# Sheet_1_2022-02-26.net
KiCad netlist of a schematic drawn in Altium Designer
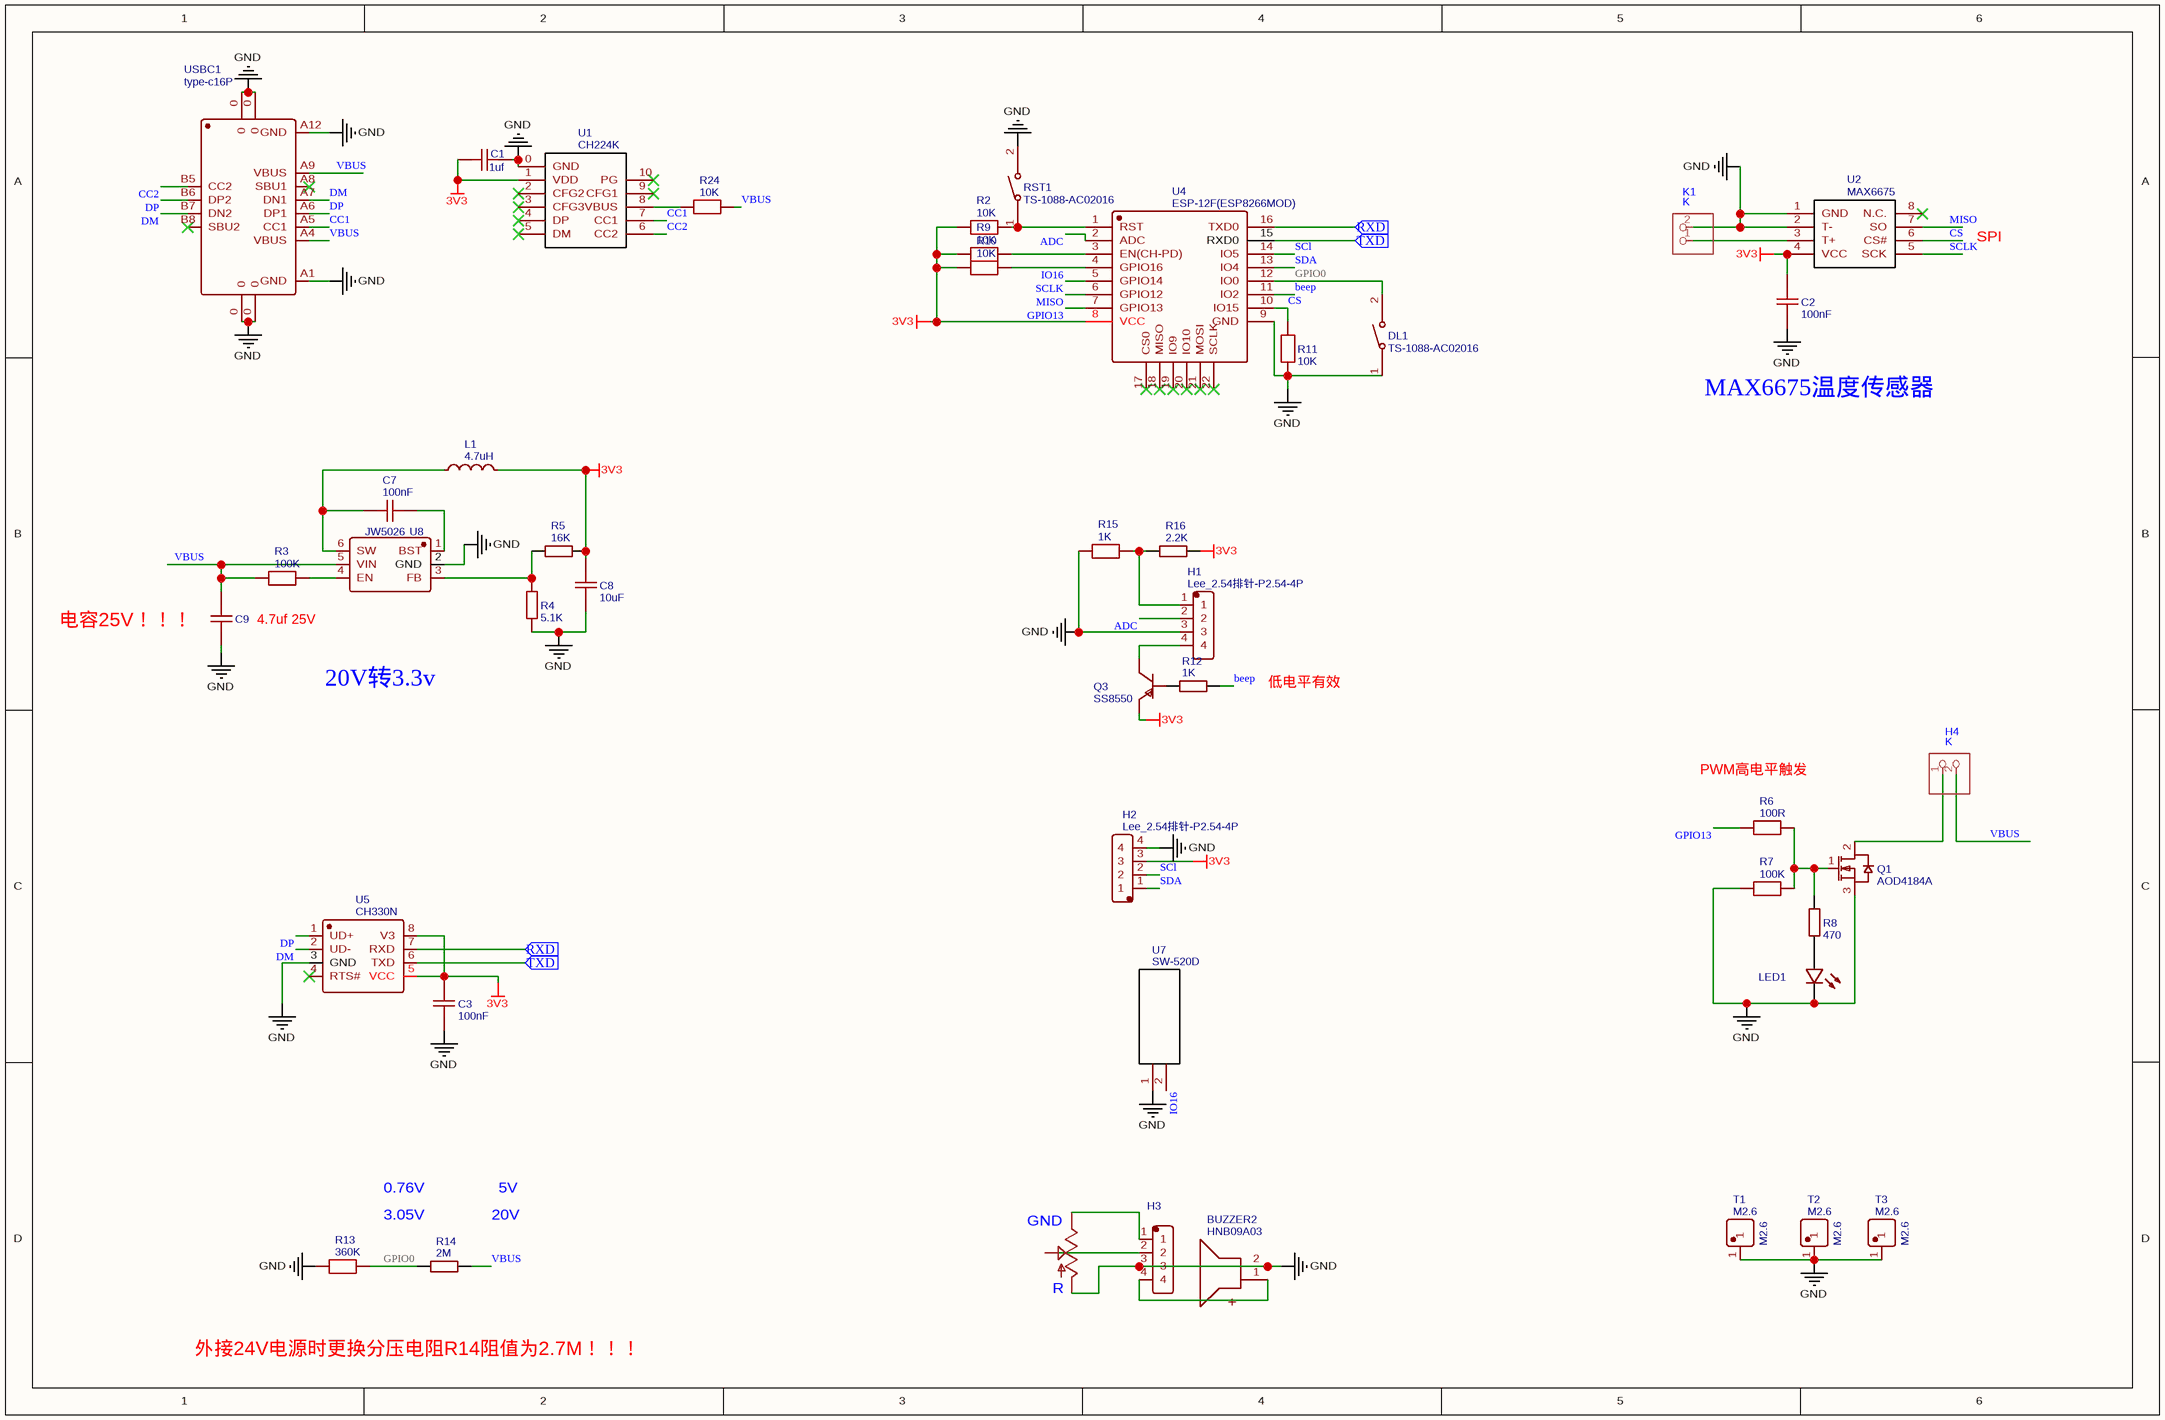
[diagram p0: Sheet_1_2022-02-26.schdoc]

(export (version "E")
  (design (tool "Eeschema 10.0.6"))
  (components
    (comp (ref "BUZZER2")
      (value "HNB09A03")
      (fields (field (name "BOM_SUPPLIER PART") "C96102") (field (name "CONTRIBUTOR") "LCSC"))
      (libsource (lib "altium-import") (part "root_0_HNB09A03_"))
    )
    (comp (ref "C1")
      (value "1uf")
      (fields (field (name "BOM_SUPPLIER PART") "C2887020") (field (name "CONTRIBUTOR") "LCEDA_Lib"))
      (libsource (lib "altium-import") (part "root_2_1uf_"))
    )
    (comp (ref "C2")
      (value "100nF")
      (fields
        (field (name "BOM_SUPPLIER PART") "C387959")
        (field (name "BOM_MANUFACTURER PART") "0402X104K500CT")
        (field (name "CONTRIBUTOR") "LCSC")
      )
      (libsource (lib "altium-import") (part "root_2_100nF_"))
    )
    (comp (ref "C3")
      (value "100nF")
      (fields
        (field (name "BOM_SUPPLIER PART") "C387959")
        (field (name "BOM_MANUFACTURER PART") "0402X104K500CT")
        (field (name "CONTRIBUTOR") "LCSC")
      )
      (libsource (lib "altium-import") (part "root_2_100nF_"))
    )
    (comp (ref "C7")
      (value "100nF")
      (fields
        (field (name "BOM_SUPPLIER PART") "C387959")
        (field (name "BOM_MANUFACTURER PART") "0402X104K500CT")
        (field (name "CONTRIBUTOR") "LCSC")
      )
      (libsource (lib "altium-import") (part "root_1_100nF_"))
    )
    (comp (ref "C8")
      (value "10uF")
      (fields
        (field (name "BOM_SUPPLIER PART") "C315248")
        (field (name "BOM_MANUFACTURER PART") "CL05A106MP5NUNC")
        (field (name "CONTRIBUTOR") "LCSC")
      )
      (libsource (lib "altium-import") (part "root_1_10uF_"))
    )
    (comp (ref "C9")
      (value "4.7uf 25V")
      (fields (field (name "BOM_SUPPLIER PART") "C2858031") (field (name "CONTRIBUTOR") "LCEDA_Lib"))
      (libsource (lib "altium-import") (part "root_1_4.7uf 25V_"))
    )
    (comp (ref "DL1")
      (value "TS-1088-AC02016")
      (fields (field (name "BOM_SUPPLIER PART") "C720475") (field (name "CONTRIBUTOR") "LCSC"))
      (libsource (lib "altium-import") (part "root_1_TS-1088-AC02016_"))
    )
    (comp (ref "H1")
      (value "Lee_2.54排针-P2.54-4P")
      (fields
        (field (name "BOM_MANUFACTURER PART") "210S-1*4P L=11.6MMGold-plated black")
        (field (name "BOM_SUPPLIER PART") "C124378")
        (field (name "CONTRIBUTOR") "EdwardLee2020")
      )
      (libsource (lib "altium-import") (part "root_0_Lee_2.54排针-P2.54-4P_"))
    )
    (comp (ref "H2")
      (value "Lee_2.54排针-P2.54-4P")
      (fields
        (field (name "BOM_MANUFACTURER PART") "210S-1*4P L=11.6MMGold-plated black")
        (field (name "BOM_SUPPLIER PART") "C124378")
        (field (name "CONTRIBUTOR") "EdwardLee2020")
      )
      (libsource (lib "altium-import") (part "root_2_Lee_2.54排针-P2.54-4P_"))
    )
    (comp (ref "H3")
      (value "Lee_2.54排针-P2.54-4P")
      (fields
        (field (name "BOM_MANUFACTURER PART") "210S-1*4P L=11.6MMGold-plated black")
        (field (name "BOM_SUPPLIER PART") "C124378")
        (field (name "CONTRIBUTOR") "EdwardLee2020")
      )
      (libsource (lib "altium-import") (part "root_0_Lee_2.54排针-P2.54-4P_"))
    )
    (comp (ref "H4")
      (value "K")
      (fields (field (name "BOM_MANUFACTURER PART") "826629-2") (field (name "BOM_SUPPLIER PART") "C86471"))
      (libsource (lib "altium-import") (part "root_1_K_"))
    )
    (comp (ref "K1")
      (value "K")
      (fields (field (name "BOM_MANUFACTURER PART") "826629-2") (field (name "BOM_SUPPLIER PART") "C86471"))
      (libsource (lib "altium-import") (part "root_2_K_"))
    )
    (comp (ref "L1")
      (value "4.7uH")
      (fields
        (field (name "BOM_MANUFACTURER PART") "SWPA252012S4R7MT")
        (field (name "BOM_SUPPLIER PART") "C87640")
      )
      (libsource (lib "altium-import") (part "root_0_4.7uH_"))
    )
    (comp (ref "LED1")
      (value "19-217/GHC-YR1S2/3T")
      (fields (field (name "BOM_SUPPLIER PART") "C181863"))
      (libsource (lib "altium-import") (part "root_3_19-217/GHC-YR1S2/3T_"))
    )
    (comp (ref "Q1")
      (value "AOD4184A")
      (fields (field (name "BOM_SUPPLIER PART") "C99124") (field (name "CONTRIBUTOR") "LCSC"))
      (libsource (lib "altium-import") (part "root_0_AOD4184A_"))
    )
    (comp (ref "Q3")
      (value "SS8550")
      (fields (field (name "BOM_SUPPLIER PART") "C266595") (field (name "CONTRIBUTOR") "SmileWJ"))
      (libsource (lib "altium-import") (part "root_2_SS8550_"))
    )
    (comp (ref "R2")
      (value "10K")
      (fields
        (field (name "BOM_SUPPLIER PART") "C830216")
        (field (name "BOM_MANUFACTURER PART") "RK73G1ETTP1002F")
        (field (name "CONTRIBUTOR") "LCSC")
      )
      (libsource (lib "altium-import") (part "root_0_10K_"))
    )
    (comp (ref "R3")
      (value "100K")
      (fields
        (field (name "BOM_SUPPLIER PART") "C606167")
        (field (name "BOM_MANUFACTURER PART") "RC0402FR-7W100KL")
        (field (name "CONTRIBUTOR") "LCSC")
      )
      (libsource (lib "altium-import") (part "root_0_100K_"))
    )
    (comp (ref "R4")
      (value "5.1K")
      (fields (field (name "BOM_SUPPLIER PART") "C25905") (field (name "CONTRIBUTOR") "LCSC"))
      (libsource (lib "altium-import") (part "root_1_5.1K_"))
    )
    (comp (ref "R5")
      (value "16K")
      (fields
        (field (name "BOM_MANUFACTURER PART") "0402WGF7501TCE")
        (field (name "BOM_SUPPLIER PART") "C226690")
      )
      (libsource (lib "altium-import") (part "root_0_16K_"))
    )
    (comp (ref "R6")
      (value "100R")
      (fields
        (field (name "BOM_SUPPLIER PART") "C705641")
        (field (name "BOM_MANUFACTURER PART") "RT0402BRE07100RL")
        (field (name "CONTRIBUTOR") "LCSC")
      )
      (libsource (lib "altium-import") (part "root_0_100R_"))
    )
    (comp (ref "R7")
      (value "100K")
      (fields
        (field (name "BOM_SUPPLIER PART") "C606167")
        (field (name "BOM_MANUFACTURER PART") "RC0402FR-7W100KL")
        (field (name "CONTRIBUTOR") "LCSC")
      )
      (libsource (lib "altium-import") (part "root_0_100K_"))
    )
    (comp (ref "R8")
      (value "470")
      (fields
        (field (name "BOM_MANUFACTURER PART") "0805W8F1002T5E")
        (field (name "BOM_SUPPLIER PART") "C17414")
      )
      (libsource (lib "altium-import") (part "root_3_470_"))
    )
    (comp (ref "R9")
      (value "10K")
      (fields
        (field (name "BOM_SUPPLIER PART") "C830216")
        (field (name "BOM_MANUFACTURER PART") "RK73G1ETTP1002F")
        (field (name "CONTRIBUTOR") "LCSC")
      )
      (libsource (lib "altium-import") (part "root_0_10K_"))
    )
    (comp (ref "R10")
      (value "10K")
      (fields
        (field (name "BOM_SUPPLIER PART") "C830216")
        (field (name "BOM_MANUFACTURER PART") "RK73G1ETTP1002F")
        (field (name "CONTRIBUTOR") "LCSC")
      )
      (libsource (lib "altium-import") (part "root_0_10K_"))
    )
    (comp (ref "R11")
      (value "10K")
      (fields
        (field (name "BOM_SUPPLIER PART") "C830216")
        (field (name "BOM_MANUFACTURER PART") "RK73G1ETTP1002F")
        (field (name "CONTRIBUTOR") "LCSC")
      )
      (libsource (lib "altium-import") (part "root_1_10K_"))
    )
    (comp (ref "R12")
      (value "1K")
      (fields
        (field (name "BOM_MANUFACTURER PART") "0805W8F1002T5E")
        (field (name "BOM_SUPPLIER PART") "C17414")
      )
      (libsource (lib "altium-import") (part "root_2_1K_"))
    )
    (comp (ref "R13")
      (value "360K")
      (fields
        (field (name "BOM_SUPPLIER PART") "C482154")
        (field (name "BOM_MANUFACTURER PART") "CRCW0402360KFKED")
        (field (name "CONTRIBUTOR") "LCSC")
      )
      (libsource (lib "altium-import") (part "root_0_360K_"))
    )
    (comp (ref "R14")
      (value "2M")
      (fields
        (field (name "BOM_MANUFACTURER PART") "0402WGF2004TCE")
        (field (name "BOM_SUPPLIER PART") "C11512")
      )
      (libsource (lib "altium-import") (part "root_0_2M_"))
    )
    (comp (ref "R15")
      (value "1K")
      (fields
        (field (name "BOM_SUPPLIER PART") "C226698")
        (field (name "BOM_MANUFACTURER PART") "AC0402DR-071KL")
        (field (name "CONTRIBUTOR") "LCSC")
      )
      (libsource (lib "altium-import") (part "root_0_1K_"))
    )
    (comp (ref "R16")
      (value "2.2K")
      (fields
        (field (name "BOM_MANUFACTURER PART") "0402WGF2201TCE")
        (field (name "BOM_SUPPLIER PART") "C25879")
      )
      (libsource (lib "altium-import") (part "root_0_2.2K_"))
    )
    (comp (ref "R24")
      (value "10K")
      (fields
        (field (name "BOM_SUPPLIER PART") "C830216")
        (field (name "BOM_MANUFACTURER PART") "RK73G1ETTP1002F")
        (field (name "CONTRIBUTOR") "LCSC")
      )
      (libsource (lib "altium-import") (part "root_0_10K_"))
    )
    (comp (ref "RST1")
      (value "TS-1088-AC02016")
      (fields (field (name "BOM_SUPPLIER PART") "C720475") (field (name "CONTRIBUTOR") "LCSC"))
      (libsource (lib "altium-import") (part "root_1_TS-1088-AC02016_"))
    )
    (comp (ref "T1")
      (value "M2.6")
      (fields (field (name "CONTRIBUTOR") "wowlkh"))
      (libsource (lib "altium-import") (part "root_1_M2.6_"))
    )
    (comp (ref "T2")
      (value "M2.6")
      (fields (field (name "CONTRIBUTOR") "wowlkh"))
      (libsource (lib "altium-import") (part "root_1_M2.6_"))
    )
    (comp (ref "T3")
      (value "M2.6")
      (fields (field (name "CONTRIBUTOR") "wowlkh"))
      (libsource (lib "altium-import") (part "root_1_M2.6_"))
    )
    (comp (ref "U1")
      (value "CH224K")
      (fields (field (name "CONTRIBUTOR") "hans_1024"))
      (libsource (lib "altium-import") (part "root_0_CH224K_"))
    )
    (comp (ref "U2")
      (value "MAX6675")
      (fields
        (field (name "BOM_MANUFACTURER PART") "MAX6675ISA+T")
        (field (name "BOM_SUPPLIER PART") "C16030")
      )
      (libsource (lib "altium-import") (part "root_0_MAX6675_"))
    )
    (comp (ref "U4")
      (value "ESP-12F(ESP8266MOD)")
      (fields (field (name "BOM_SUPPLIER PART") "C82891"))
      (libsource (lib "altium-import") (part "root_0_ESP-12F(ESP8266MOD)_"))
    )
    (comp (ref "U5")
      (value "CH330N")
      (fields (field (name "BOM_SUPPLIER PART") "C108996"))
      (libsource (lib "altium-import") (part "root_0_CH330N_"))
    )
    (comp (ref "U7")
      (value "SW-520D")
      (fields (field (name "CONTRIBUTOR") "jimson.hu"))
      (libsource (lib "altium-import") (part "root_0_SW-520D_"))
    )
    (comp (ref "U8")
      (value "JW5026")
      (fields (field (name "BOM_SUPPLIER PART") "C185109") (field (name "CONTRIBUTOR") "LCSC"))
      (libsource (lib "altium-import") (part "root_0_JW5026_"))
    )
    (comp (ref "U10")
      (value "B103单联")
      (fields (field (name "CONTRIBUTOR") "lualiliu"))
      (libsource (lib "altium-import") (part "root_2_B103单联_"))
    )
    (comp (ref "USBC1")
      (value "type-c16P")
      (fields (field (name "BOM_SUPPLIER PART") "C167321") (field (name "CONTRIBUTOR") "LCSC"))
      (libsource (lib "altium-import") (part "root_0_type-c16P_"))
    )
  )
  (nets
    (net (code "1") (name "/ADC") (class "Default")
      (node (ref "H1") (pin "2") (pinfunction "2_2") (pintype "passive"))
      (node (ref "U4") (pin "2") (pinfunction "ADC_2") (pintype "passive"))
    )
    (net (code "2") (name "/CC1") (class "Default")
      (node (ref "U1") (pin "7") (pinfunction "CC1_7") (pintype "passive"))
      (node (ref "USBC1") (pin "A5") (pinfunction "CC1_A5") (pintype "passive"))
    )
    (net (code "3") (name "/CC2") (class "Default")
      (node (ref "U1") (pin "6") (pinfunction "CC2_6") (pintype "passive"))
      (node (ref "USBC1") (pin "B5") (pinfunction "CC2_B5") (pintype "passive"))
    )
    (net (code "4") (name "/CS") (class "Default")
      (node (ref "R11") (pin "2") (pinfunction "2_2") (pintype "passive"))
      (node (ref "U2") (pin "6") (pinfunction "CS#_6") (pintype "passive"))
      (node (ref "U4") (pin "10") (pinfunction "IO15_10") (pintype "passive"))
    )
    (net (code "5") (name "/DM") (class "Default")
      (node (ref "U5") (pin "2") (pinfunction "UD-_2") (pintype "passive"))
      (node (ref "USBC1") (pin "A7") (pinfunction "DN1_A7") (pintype "passive"))
      (node (ref "USBC1") (pin "B7") (pinfunction "DN2_B7") (pintype "passive"))
    )
    (net (code "6") (name "/DP") (class "Default")
      (node (ref "U5") (pin "1") (pinfunction "UD+_1") (pintype "passive"))
      (node (ref "USBC1") (pin "A6") (pinfunction "DP1_A6") (pintype "passive"))
      (node (ref "USBC1") (pin "B6") (pinfunction "DP2_B6") (pintype "passive"))
    )
    (net (code "7") (name "/GPIO0") (class "Default")
      (node (ref "DL1") (pin "2") (pinfunction "2_2") (pintype "passive"))
      (node (ref "R13") (pin "2") (pinfunction "2_2") (pintype "passive"))
      (node (ref "R14") (pin "1") (pinfunction "1_1") (pintype "passive"))
      (node (ref "U4") (pin "12") (pinfunction "IO0_12") (pintype "passive"))
    )
    (net (code "8") (name "/GPIO13") (class "Default")
      (node (ref "R6") (pin "1") (pinfunction "1_1") (pintype "passive"))
      (node (ref "U4") (pin "7") (pinfunction "GPIO13_7") (pintype "passive"))
    )
    (net (code "9") (name "/IO16") (class "Default")
      (node (ref "R10") (pin "2") (pinfunction "2_2") (pintype "passive"))
      (node (ref "U4") (pin "4") (pinfunction "GPIO16_4") (pintype "passive"))
      (node (ref "U7") (pin "2") (pinfunction "2_2") (pintype "passive"))
    )
    (net (code "10") (name "/MISO") (class "Default")
      (node (ref "U2") (pin "7") (pinfunction "SO_7") (pintype "passive"))
      (node (ref "U4") (pin "6") (pinfunction "GPIO12_6") (pintype "passive"))
    )
    (net (code "11") (name "/RXD") (class "Default")
      (node (ref "U4") (pin "16") (pinfunction "TXD0_16") (pintype "passive"))
      (node (ref "U5") (pin "7") (pinfunction "RXD_7") (pintype "passive"))
    )
    (net (code "12") (name "/SCLK") (class "Default")
      (node (ref "U2") (pin "5") (pinfunction "SCK_5") (pintype "passive"))
      (node (ref "U4") (pin "5") (pinfunction "GPIO14_5") (pintype "passive"))
    )
    (net (code "13") (name "/SCl") (class "Default")
      (node (ref "H2") (pin "2") (pinfunction "2_2") (pintype "passive"))
      (node (ref "U4") (pin "14") (pinfunction "IO5_14") (pintype "passive"))
    )
    (net (code "14") (name "/SDA") (class "Default")
      (node (ref "H2") (pin "1") (pinfunction "1_1") (pintype "passive"))
      (node (ref "U4") (pin "13") (pinfunction "IO4_13") (pintype "passive"))
    )
    (net (code "15") (name "/TXD") (class "Default")
      (node (ref "U4") (pin "15") (pinfunction "RXD0_15") (pintype "passive"))
      (node (ref "U5") (pin "6") (pinfunction "TXD_6") (pintype "passive"))
    )
    (net (code "16") (name "/VBUS") (class "Default")
      (node (ref "C9") (pin "2") (pinfunction "2_2") (pintype "passive"))
      (node (ref "H4") (pin "2") (pinfunction "2_2") (pintype "passive"))
      (node (ref "R14") (pin "2") (pinfunction "2_2") (pintype "passive"))
      (node (ref "R24") (pin "2") (pinfunction "2_2") (pintype "passive"))
      (node (ref "R3") (pin "1") (pinfunction "1_1") (pintype "passive"))
      (node (ref "U8") (pin "5") (pinfunction "VIN_5") (pintype "passive"))
      (node (ref "USBC1") (pin "A4") (pinfunction "VBUS_A4") (pintype "passive"))
      (node (ref "USBC1") (pin "A9") (pinfunction "VBUS_A9") (pintype "passive"))
    )
    (net (code "17") (name "/beep") (class "Default")
      (node (ref "R12") (pin "1") (pinfunction "1_1") (pintype "passive"))
      (node (ref "U4") (pin "11") (pinfunction "IO2_11") (pintype "passive"))
    )
    (net (code "18") (name "3V3") (class "Default")
      (node (ref "C1") (pin "2") (pinfunction "2_2") (pintype "passive"))
      (node (ref "C2") (pin "1") (pinfunction "1_1") (pintype "passive"))
      (node (ref "C3") (pin "1") (pinfunction "1_1") (pintype "passive"))
      (node (ref "C8") (pin "2") (pinfunction "2_2") (pintype "passive"))
      (node (ref "H2") (pin "3") (pinfunction "3_3") (pintype "passive"))
      (node (ref "L1") (pin "2") (pinfunction "2_2") (pintype "passive"))
      (node (ref "Q3") (pin "3") (pinfunction "C_3") (pintype "passive"))
      (node (ref "R10") (pin "1") (pinfunction "1_1") (pintype "passive"))
      (node (ref "R16") (pin "2") (pinfunction "2_2") (pintype "passive"))
      (node (ref "R2") (pin "1") (pinfunction "1_1") (pintype "passive"))
      (node (ref "R5") (pin "2") (pinfunction "2_2") (pintype "passive"))
      (node (ref "R9") (pin "1") (pinfunction "1_1") (pintype "passive"))
      (node (ref "U1") (pin "1") (pinfunction "VDD_1") (pintype "passive"))
      (node (ref "U2") (pin "4") (pinfunction "VCC_4") (pintype "passive"))
      (node (ref "U4") (pin "8") (pinfunction "VCC_8") (pintype "passive"))
      (node (ref "U5") (pin "5") (pinfunction "VCC_5") (pintype "passive"))
      (node (ref "U5") (pin "8") (pinfunction "V3_8") (pintype "passive"))
    )
    (net (code "19") (name "GND") (class "Default")
      (node (ref "BUZZER2") (pin "2") (pinfunction "-_2") (pintype "passive"))
      (node (ref "C1") (pin "1") (pinfunction "1_1") (pintype "passive"))
      (node (ref "C2") (pin "2") (pinfunction "2_2") (pintype "passive"))
      (node (ref "C3") (pin "2") (pinfunction "2_2") (pintype "passive"))
      (node (ref "C8") (pin "1") (pinfunction "1_1") (pintype "passive"))
      (node (ref "C9") (pin "1") (pinfunction "1_1") (pintype "passive"))
      (node (ref "DL1") (pin "1") (pinfunction "1_1") (pintype "passive"))
      (node (ref "H1") (pin "3") (pinfunction "3_3") (pintype "passive"))
      (node (ref "H2") (pin "4") (pinfunction "4_4") (pintype "passive"))
      (node (ref "H3") (pin "3") (pinfunction "3_3") (pintype "passive"))
      (node (ref "K1") (pin "2") (pinfunction "2_2") (pintype "passive"))
      (node (ref "LED1") (pin "2") (pinfunction "C_2") (pintype "passive"))
      (node (ref "Q1") (pin "3") (pinfunction "S_3") (pintype "passive"))
      (node (ref "R11") (pin "1") (pinfunction "1_1") (pintype "passive"))
      (node (ref "R13") (pin "1") (pinfunction "1_1") (pintype "passive"))
      (node (ref "R15") (pin "1") (pinfunction "1_1") (pintype "passive"))
      (node (ref "R4") (pin "1") (pinfunction "1_1") (pintype "passive"))
      (node (ref "R7") (pin "1") (pinfunction "1_1") (pintype "passive"))
      (node (ref "RST1") (pin "2") (pinfunction "2_2") (pintype "passive"))
      (node (ref "T1") (pin "1") (pinfunction "1_1") (pintype "passive"))
      (node (ref "T2") (pin "1") (pinfunction "1_1") (pintype "passive"))
      (node (ref "T3") (pin "1") (pinfunction "1_1") (pintype "passive"))
      (node (ref "U1") (pin "0") (pinfunction "GND_0") (pintype "passive"))
      (node (ref "U10") (pin "3") (pinfunction "A_3") (pintype "passive"))
      (node (ref "U2") (pin "1") (pinfunction "GND_1") (pintype "passive"))
      (node (ref "U2") (pin "2") (pinfunction "T-_2") (pintype "passive"))
      (node (ref "U4") (pin "9") (pinfunction "GND_9") (pintype "passive"))
      (node (ref "U5") (pin "3") (pinfunction "GND_3") (pintype "passive"))
      (node (ref "U7") (pin "1") (pinfunction "1_1") (pintype "passive"))
      (node (ref "U8") (pin "2") (pinfunction "GND_2") (pintype "passive"))
      (node (ref "USBC1") (pin "0") (pinfunction "0_0") (pintype "passive"))
      (node (ref "USBC1") (pin "A1") (pinfunction "GND_A1") (pintype "passive"))
      (node (ref "USBC1") (pin "A12") (pinfunction "GND_A12") (pintype "passive"))
    )
    (net (code "20") (name "Net-(BUZZER2-+)") (class "Default")
      (node (ref "BUZZER2") (pin "1") (pinfunction "+_1") (pintype "passive"))
      (node (ref "H3") (pin "4") (pinfunction "4_4") (pintype "passive"))
    )
    (net (code "21") (name "Net-(H1-Pad1)") (class "Default")
      (node (ref "H1") (pin "1") (pinfunction "1_1") (pintype "passive"))
      (node (ref "R15") (pin "2") (pinfunction "2_2") (pintype "passive"))
      (node (ref "R16") (pin "1") (pinfunction "1_1") (pintype "passive"))
    )
    (net (code "22") (name "Net-(LED1-A)") (class "Default")
      (node (ref "LED1") (pin "1") (pinfunction "A_1") (pintype "passive"))
      (node (ref "R8") (pin "2") (pinfunction "2_2") (pintype "passive"))
    )
    (net (code "23") (name "Net-(Q1-D)") (class "Default")
      (node (ref "H4") (pin "1") (pinfunction "1_1") (pintype "passive"))
      (node (ref "Q1") (pin "2") (pinfunction "D_2") (pintype "passive"))
    )
    (net (code "24") (name "Net-(Q1-G)") (class "Default")
      (node (ref "Q1") (pin "1") (pinfunction "G_1") (pintype "passive"))
      (node (ref "R6") (pin "2") (pinfunction "2_2") (pintype "passive"))
      (node (ref "R7") (pin "2") (pinfunction "2_2") (pintype "passive"))
      (node (ref "R8") (pin "1") (pinfunction "1_1") (pintype "passive"))
    )
    (net (code "25") (name "Net-(Q3-B)") (class "Default")
      (node (ref "Q3") (pin "1") (pinfunction "B_1") (pintype "passive"))
      (node (ref "R12") (pin "2") (pinfunction "2_2") (pintype "passive"))
    )
    (net (code "26") (name "Net-(Q3-E)") (class "Default")
      (node (ref "H1") (pin "4") (pinfunction "4_4") (pintype "passive"))
      (node (ref "Q3") (pin "2") (pinfunction "E_2") (pintype "passive"))
    )
    (net (code "27") (name "Net-(U1-VBUS)") (class "Default")
      (node (ref "R24") (pin "1") (pinfunction "1_1") (pintype "passive"))
      (node (ref "U1") (pin "8") (pinfunction "VBUS_8") (pintype "passive"))
    )
    (net (code "28") (name "Net-(U2-T+)") (class "Default")
      (node (ref "K1") (pin "1") (pinfunction "1_1") (pintype "passive"))
      (node (ref "U2") (pin "3") (pinfunction "T+_3") (pintype "passive"))
    )
    (net (code "29") (name "Net-(U4-EN(CH-PD))") (class "Default")
      (node (ref "R9") (pin "2") (pinfunction "2_2") (pintype "passive"))
      (node (ref "U4") (pin "3") (pinfunction "EN(CH-PD)_3") (pintype "passive"))
    )
    (net (code "30") (name "Net-(U4-RST)") (class "Default")
      (node (ref "R2") (pin "2") (pinfunction "2_2") (pintype "passive"))
      (node (ref "RST1") (pin "1") (pinfunction "1_1") (pintype "passive"))
      (node (ref "U4") (pin "1") (pinfunction "RST_1") (pintype "passive"))
    )
    (net (code "31") (name "Net-(U8-BST)") (class "Default")
      (node (ref "C7") (pin "1") (pinfunction "1_1") (pintype "passive"))
      (node (ref "U8") (pin "1") (pinfunction "BST_1") (pintype "passive"))
    )
    (net (code "32") (name "Net-(U8-EN)") (class "Default")
      (node (ref "R3") (pin "2") (pinfunction "2_2") (pintype "passive"))
      (node (ref "U8") (pin "4") (pinfunction "EN_4") (pintype "passive"))
    )
    (net (code "33") (name "Net-(U8-FB)") (class "Default")
      (node (ref "R4") (pin "2") (pinfunction "2_2") (pintype "passive"))
      (node (ref "R5") (pin "1") (pinfunction "1_1") (pintype "passive"))
      (node (ref "U8") (pin "3") (pinfunction "FB_3") (pintype "passive"))
    )
    (net (code "34") (name "Net-(U8-SW)") (class "Default")
      (node (ref "C7") (pin "2") (pinfunction "2_2") (pintype "passive"))
      (node (ref "L1") (pin "1") (pinfunction "1_1") (pintype "passive"))
      (node (ref "U8") (pin "6") (pinfunction "SW_6") (pintype "passive"))
    )
    (net (code "35") (name "Net-(U10-E)") (class "Default")
      (node (ref "H3") (pin "1") (pinfunction "1_1") (pintype "passive"))
      (node (ref "U10") (pin "1") (pinfunction "E_1") (pintype "passive"))
    )
    (net (code "36") (name "Net-(U10-S)") (class "Default")
      (node (ref "H3") (pin "2") (pinfunction "2_2") (pintype "passive"))
      (node (ref "U10") (pin "2") (pinfunction "S_2") (pintype "passive"))
    )
    (net (code "37") (name "unconnected-(U1-CFG1-Pad9)") (class "Default")
      (node (ref "U1") (pin "9") (pinfunction "CFG1_9") (pintype "passive+no_connect"))
    )
    (net (code "38") (name "unconnected-(U1-CFG2-Pad2)") (class "Default")
      (node (ref "U1") (pin "2") (pinfunction "CFG2_2") (pintype "passive+no_connect"))
    )
    (net (code "39") (name "unconnected-(U1-CFG3-Pad3)") (class "Default")
      (node (ref "U1") (pin "3") (pinfunction "CFG3_3") (pintype "passive+no_connect"))
    )
    (net (code "40") (name "unconnected-(U1-DM-Pad5)") (class "Default")
      (node (ref "U1") (pin "5") (pinfunction "DM_5") (pintype "passive+no_connect"))
    )
    (net (code "41") (name "unconnected-(U1-DP-Pad4)") (class "Default")
      (node (ref "U1") (pin "4") (pinfunction "DP_4") (pintype "passive+no_connect"))
    )
    (net (code "42") (name "unconnected-(U1-PG-Pad10)") (class "Default")
      (node (ref "U1") (pin "10") (pinfunction "PG_10") (pintype "passive+no_connect"))
    )
    (net (code "43") (name "unconnected-(U2-N.C.-Pad8)") (class "Default")
      (node (ref "U2") (pin "8") (pinfunction "N.C._8") (pintype "passive+no_connect"))
    )
    (net (code "44") (name "unconnected-(U4-CS0-Pad17)") (class "Default")
      (node (ref "U4") (pin "17") (pinfunction "CS0_17") (pintype "passive+no_connect"))
    )
    (net (code "45") (name "unconnected-(U4-IO9-Pad19)") (class "Default")
      (node (ref "U4") (pin "19") (pinfunction "IO9_19") (pintype "passive+no_connect"))
    )
    (net (code "46") (name "unconnected-(U4-IO10-Pad20)") (class "Default")
      (node (ref "U4") (pin "20") (pinfunction "IO10_20") (pintype "passive+no_connect"))
    )
    (net (code "47") (name "unconnected-(U4-MISO-Pad18)") (class "Default")
      (node (ref "U4") (pin "18") (pinfunction "MISO_18") (pintype "passive+no_connect"))
    )
    (net (code "48") (name "unconnected-(U4-MOSI-Pad21)") (class "Default")
      (node (ref "U4") (pin "21") (pinfunction "MOSI_21") (pintype "passive+no_connect"))
    )
    (net (code "49") (name "unconnected-(U4-SCLK-Pad22)") (class "Default")
      (node (ref "U4") (pin "22") (pinfunction "SCLK_22") (pintype "passive+no_connect"))
    )
    (net (code "50") (name "unconnected-(U5-RTS#-Pad4)") (class "Default")
      (node (ref "U5") (pin "4") (pinfunction "RTS#_4") (pintype "passive+no_connect"))
    )
    (net (code "51") (name "unconnected-(USBC1-SBU1-PadA8)") (class "Default")
      (node (ref "USBC1") (pin "A8") (pinfunction "SBU1_A8") (pintype "passive+no_connect"))
    )
    (net (code "52") (name "unconnected-(USBC1-SBU2-PadB8)") (class "Default")
      (node (ref "USBC1") (pin "B8") (pinfunction "SBU2_B8") (pintype "passive+no_connect"))
    )
  )
)
